# Buck_60W20V_Power_Section.net
KiCad netlist of a schematic drawn in Altium Designer
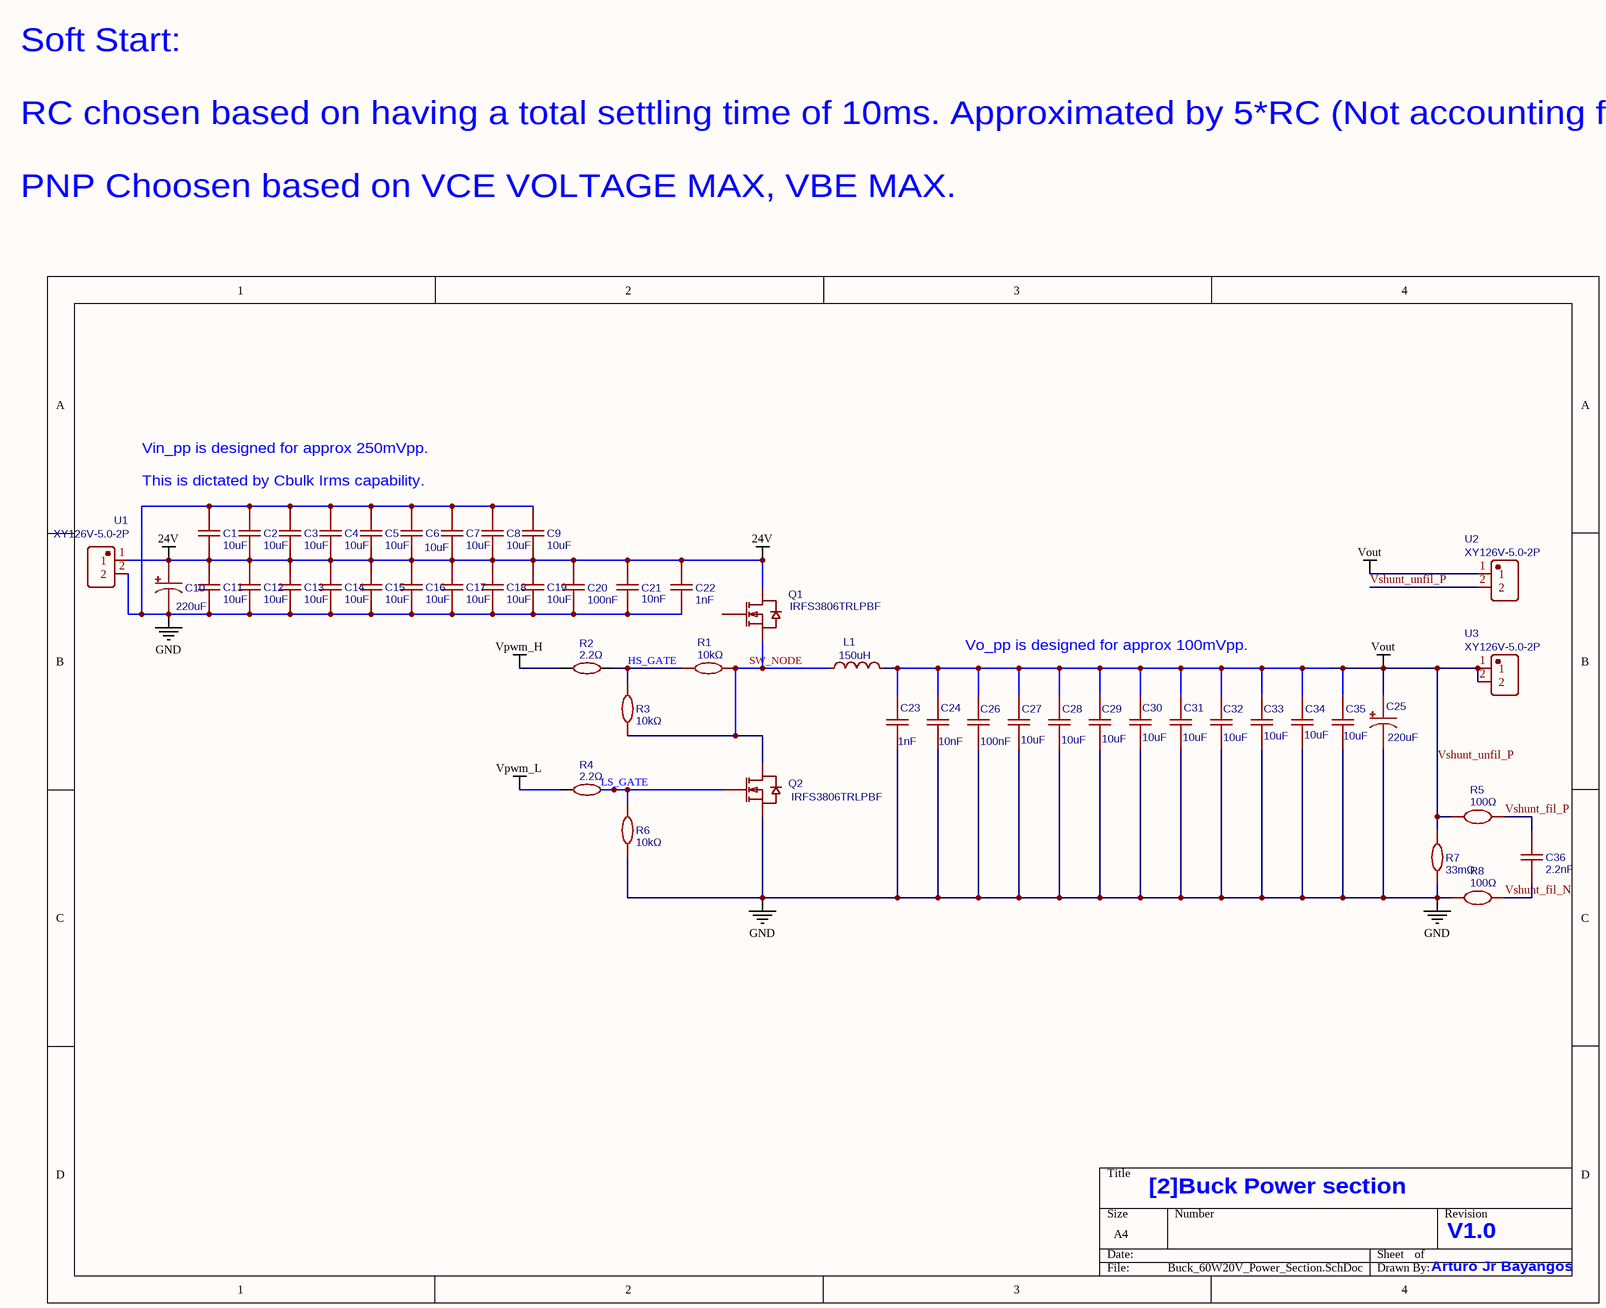
[diagram p0: Buck_60W20V_Power_Section.SchDoc]

(export (version "E")
  (design (tool "Eeschema 10.0.6"))
  (components
    (comp (ref "C1")
      (value "10uF")
      (footprint "C1210")
      (fields
        (field (name "MANUFACTURER") "TAIYO YUDEN(太诱)")
        (field (name "MANUFACTURER PART") "UMK325AB7106KM-T")
        (field (name "CONTRIBUTOR") "LCSC")
      )
      (libsource (lib "altium-import") (part "root_1_10uF_"))
    )
    (comp (ref "C2")
      (value "10uF")
      (footprint "C1210")
      (fields
        (field (name "MANUFACTURER") "TAIYO YUDEN(太诱)")
        (field (name "MANUFACTURER PART") "UMK325AB7106KM-T")
        (field (name "CONTRIBUTOR") "LCSC")
      )
      (libsource (lib "altium-import") (part "root_1_10uF_"))
    )
    (comp (ref "C3")
      (value "10uF")
      (footprint "C1210")
      (fields
        (field (name "MANUFACTURER") "TAIYO YUDEN(太诱)")
        (field (name "MANUFACTURER PART") "UMK325AB7106KM-T")
        (field (name "CONTRIBUTOR") "LCSC")
      )
      (libsource (lib "altium-import") (part "root_1_10uF_"))
    )
    (comp (ref "C4")
      (value "10uF")
      (footprint "C1210")
      (fields
        (field (name "MANUFACTURER") "TAIYO YUDEN(太诱)")
        (field (name "MANUFACTURER PART") "UMK325AB7106KM-T")
        (field (name "CONTRIBUTOR") "LCSC")
      )
      (libsource (lib "altium-import") (part "root_1_10uF_"))
    )
    (comp (ref "C5")
      (value "10uF")
      (footprint "C1210")
      (fields
        (field (name "MANUFACTURER") "TAIYO YUDEN(太诱)")
        (field (name "MANUFACTURER PART") "UMK325AB7106KM-T")
        (field (name "CONTRIBUTOR") "LCSC")
      )
      (libsource (lib "altium-import") (part "root_1_10uF_"))
    )
    (comp (ref "C6")
      (value "10uF")
      (footprint "C1210")
      (fields
        (field (name "MANUFACTURER") "TAIYO YUDEN(太诱)")
        (field (name "MANUFACTURER PART") "UMK325AB7106KM-T")
        (field (name "CONTRIBUTOR") "LCSC")
      )
      (libsource (lib "altium-import") (part "root_1_10uF_"))
    )
    (comp (ref "C7")
      (value "10uF")
      (footprint "C1210")
      (fields
        (field (name "MANUFACTURER") "TAIYO YUDEN(太诱)")
        (field (name "MANUFACTURER PART") "UMK325AB7106KM-T")
        (field (name "CONTRIBUTOR") "LCSC")
      )
      (libsource (lib "altium-import") (part "root_1_10uF_"))
    )
    (comp (ref "C8")
      (value "10uF")
      (footprint "C1210")
      (fields
        (field (name "MANUFACTURER") "TAIYO YUDEN(太诱)")
        (field (name "MANUFACTURER PART") "UMK325AB7106KM-T")
        (field (name "CONTRIBUTOR") "LCSC")
      )
      (libsource (lib "altium-import") (part "root_1_10uF_"))
    )
    (comp (ref "C9")
      (value "10uF")
      (footprint "C1210")
      (fields
        (field (name "MANUFACTURER") "TAIYO YUDEN(太诱)")
        (field (name "MANUFACTURER PART") "UMK325AB7106KM-T")
        (field (name "CONTRIBUTOR") "LCSC")
      )
      (libsource (lib "altium-import") (part "root_1_10uF_"))
    )
    (comp (ref "C10")
      (value "220uF")
      (footprint "CAP-SMD_BD10.0-L10.3-W10.3-LS11.3-FD")
      (fields
        (field (name "MANUFACTURER") "Nichicon(尼吉康)")
        (field (name "MANUFACTURER PART") "UUD1H221MNL1GS")
        (field (name "CONTRIBUTOR") "LCSC")
      )
      (libsource (lib "altium-import") (part "root_0_220uF_"))
    )
    (comp (ref "C11")
      (value "10uF")
      (footprint "C1210")
      (fields
        (field (name "MANUFACTURER") "TAIYO YUDEN(太诱)")
        (field (name "MANUFACTURER PART") "UMK325AB7106KM-T")
        (field (name "CONTRIBUTOR") "LCSC")
      )
      (libsource (lib "altium-import") (part "root_1_10uF_"))
    )
    (comp (ref "C12")
      (value "10uF")
      (footprint "C1210")
      (fields
        (field (name "MANUFACTURER") "TAIYO YUDEN(太诱)")
        (field (name "MANUFACTURER PART") "UMK325AB7106KM-T")
        (field (name "CONTRIBUTOR") "LCSC")
      )
      (libsource (lib "altium-import") (part "root_1_10uF_"))
    )
    (comp (ref "C13")
      (value "10uF")
      (footprint "C1210")
      (fields
        (field (name "MANUFACTURER") "TAIYO YUDEN(太诱)")
        (field (name "MANUFACTURER PART") "UMK325AB7106KM-T")
        (field (name "CONTRIBUTOR") "LCSC")
      )
      (libsource (lib "altium-import") (part "root_1_10uF_"))
    )
    (comp (ref "C14")
      (value "10uF")
      (footprint "C1210")
      (fields
        (field (name "MANUFACTURER") "TAIYO YUDEN(太诱)")
        (field (name "MANUFACTURER PART") "UMK325AB7106KM-T")
        (field (name "CONTRIBUTOR") "LCSC")
      )
      (libsource (lib "altium-import") (part "root_1_10uF_"))
    )
    (comp (ref "C15")
      (value "10uF")
      (footprint "C1210")
      (fields
        (field (name "MANUFACTURER") "TAIYO YUDEN(太诱)")
        (field (name "MANUFACTURER PART") "UMK325AB7106KM-T")
        (field (name "CONTRIBUTOR") "LCSC")
      )
      (libsource (lib "altium-import") (part "root_1_10uF_"))
    )
    (comp (ref "C16")
      (value "10uF")
      (footprint "C1210")
      (fields
        (field (name "MANUFACTURER") "TAIYO YUDEN(太诱)")
        (field (name "MANUFACTURER PART") "UMK325AB7106KM-T")
        (field (name "CONTRIBUTOR") "LCSC")
      )
      (libsource (lib "altium-import") (part "root_1_10uF_"))
    )
    (comp (ref "C17")
      (value "10uF")
      (footprint "C1210")
      (fields
        (field (name "MANUFACTURER") "TAIYO YUDEN(太诱)")
        (field (name "MANUFACTURER PART") "UMK325AB7106KM-T")
        (field (name "CONTRIBUTOR") "LCSC")
      )
      (libsource (lib "altium-import") (part "root_1_10uF_"))
    )
    (comp (ref "C18")
      (value "10uF")
      (footprint "C1210")
      (fields
        (field (name "MANUFACTURER") "TAIYO YUDEN(太诱)")
        (field (name "MANUFACTURER PART") "UMK325AB7106KM-T")
        (field (name "CONTRIBUTOR") "LCSC")
      )
      (libsource (lib "altium-import") (part "root_1_10uF_"))
    )
    (comp (ref "C19")
      (value "10uF")
      (footprint "C1210")
      (fields
        (field (name "MANUFACTURER") "TAIYO YUDEN(太诱)")
        (field (name "MANUFACTURER PART") "UMK325AB7106KM-T")
        (field (name "CONTRIBUTOR") "LCSC")
      )
      (libsource (lib "altium-import") (part "root_1_10uF_"))
    )
    (comp (ref "C20")
      (value "100nF")
      (footprint "C0402")
      (fields
        (field (name "MANUFACTURER") "TAIYO YUDEN(太诱)")
        (field (name "MANUFACTURER PART") "UMK105B7104KV-FR")
        (field (name "CONTRIBUTOR") "lcsc")
      )
      (libsource (lib "altium-import") (part "root_1_100nF_"))
    )
    (comp (ref "C21")
      (value "10nF")
      (footprint "C0402")
      (fields
        (field (name "MANUFACTURER") "TAIYO YUDEN(太诱)")
        (field (name "MANUFACTURER PART") "UMF105B7103KVHF")
        (field (name "CONTRIBUTOR") "LCSC")
      )
      (libsource (lib "altium-import") (part "root_0_10nF_"))
    )
    (comp (ref "C22")
      (value "1nF")
      (footprint "C0402")
      (fields
        (field (name "MANUFACTURER") "TAIYO YUDEN(太诱)")
        (field (name "MANUFACTURER PART") "UMF105B7102KVHF")
        (field (name "CONTRIBUTOR") "LCSC")
      )
      (libsource (lib "altium-import") (part "root_0_1nF_"))
    )
    (comp (ref "C23")
      (value "1nF")
      (footprint "C0402")
      (fields
        (field (name "MANUFACTURER") "TAIYO YUDEN(太诱)")
        (field (name "MANUFACTURER PART") "UMF105B7102KVHF")
        (field (name "CONTRIBUTOR") "LCSC")
      )
      (libsource (lib "altium-import") (part "root_0_1nF_"))
    )
    (comp (ref "C24")
      (value "10nF")
      (footprint "C0402")
      (fields
        (field (name "MANUFACTURER") "TAIYO YUDEN(太诱)")
        (field (name "MANUFACTURER PART") "UMF105B7103KVHF")
        (field (name "CONTRIBUTOR") "LCSC")
      )
      (libsource (lib "altium-import") (part "root_0_10nF_"))
    )
    (comp (ref "C25")
      (value "220uF")
      (footprint "CAP-SMD_BD10.0-L10.3-W10.3-LS11.3-FD")
      (fields
        (field (name "MANUFACTURER") "Nichicon(尼吉康)")
        (field (name "MANUFACTURER PART") "UUD1H221MNL1GS")
        (field (name "CONTRIBUTOR") "LCSC")
      )
      (libsource (lib "altium-import") (part "root_0_220uF_"))
    )
    (comp (ref "C26")
      (value "100nF")
      (footprint "C0402")
      (fields
        (field (name "MANUFACTURER") "TAIYO YUDEN(太诱)")
        (field (name "MANUFACTURER PART") "UMK105B7104KV-FR")
        (field (name "CONTRIBUTOR") "lcsc")
      )
      (libsource (lib "altium-import") (part "root_1_100nF_"))
    )
    (comp (ref "C27")
      (value "10uF")
      (footprint "C1210")
      (fields
        (field (name "MANUFACTURER") "TAIYO YUDEN(太诱)")
        (field (name "MANUFACTURER PART") "UMK325AB7106KM-T")
        (field (name "CONTRIBUTOR") "LCSC")
      )
      (libsource (lib "altium-import") (part "root_1_10uF_"))
    )
    (comp (ref "C28")
      (value "10uF")
      (footprint "C1210")
      (fields
        (field (name "MANUFACTURER") "TAIYO YUDEN(太诱)")
        (field (name "MANUFACTURER PART") "UMK325AB7106KM-T")
        (field (name "CONTRIBUTOR") "LCSC")
      )
      (libsource (lib "altium-import") (part "root_1_10uF_"))
    )
    (comp (ref "C29")
      (value "10uF")
      (footprint "C1210")
      (fields
        (field (name "MANUFACTURER") "TAIYO YUDEN(太诱)")
        (field (name "MANUFACTURER PART") "UMK325AB7106KM-T")
        (field (name "CONTRIBUTOR") "LCSC")
      )
      (libsource (lib "altium-import") (part "root_1_10uF_"))
    )
    (comp (ref "C30")
      (value "10uF")
      (footprint "C1210")
      (fields
        (field (name "MANUFACTURER") "TAIYO YUDEN(太诱)")
        (field (name "MANUFACTURER PART") "UMK325AB7106KM-T")
        (field (name "CONTRIBUTOR") "LCSC")
      )
      (libsource (lib "altium-import") (part "root_1_10uF_"))
    )
    (comp (ref "C31")
      (value "10uF")
      (footprint "C1210")
      (fields
        (field (name "MANUFACTURER") "TAIYO YUDEN(太诱)")
        (field (name "MANUFACTURER PART") "UMK325AB7106KM-T")
        (field (name "CONTRIBUTOR") "LCSC")
      )
      (libsource (lib "altium-import") (part "root_1_10uF_"))
    )
    (comp (ref "C32")
      (value "10uF")
      (footprint "C1210")
      (fields
        (field (name "MANUFACTURER") "TAIYO YUDEN(太诱)")
        (field (name "MANUFACTURER PART") "UMK325AB7106KM-T")
        (field (name "CONTRIBUTOR") "LCSC")
      )
      (libsource (lib "altium-import") (part "root_1_10uF_"))
    )
    (comp (ref "C33")
      (value "10uF")
      (footprint "C1210")
      (fields
        (field (name "MANUFACTURER") "TAIYO YUDEN(太诱)")
        (field (name "MANUFACTURER PART") "UMK325AB7106KM-T")
        (field (name "CONTRIBUTOR") "LCSC")
      )
      (libsource (lib "altium-import") (part "root_1_10uF_"))
    )
    (comp (ref "C34")
      (value "10uF")
      (footprint "C1210")
      (fields
        (field (name "MANUFACTURER") "TAIYO YUDEN(太诱)")
        (field (name "MANUFACTURER PART") "UMK325AB7106KM-T")
        (field (name "CONTRIBUTOR") "LCSC")
      )
      (libsource (lib "altium-import") (part "root_1_10uF_"))
    )
    (comp (ref "C35")
      (value "10uF")
      (footprint "C1210")
      (fields
        (field (name "MANUFACTURER") "TAIYO YUDEN(太诱)")
        (field (name "MANUFACTURER PART") "UMK325AB7106KM-T")
        (field (name "CONTRIBUTOR") "LCSC")
      )
      (libsource (lib "altium-import") (part "root_1_10uF_"))
    )
    (comp (ref "C36")
      (value "2.2nF")
      (footprint "C0603")
      (fields
        (field (name "MANUFACTURER") "TDK")
        (field (name "MANUFACTURER PART") "C1608C0G2E222JT000N")
        (field (name "CONTRIBUTOR") "LCSC")
      )
      (libsource (lib "altium-import") (part "root_1_2.2nF_"))
    )
    (comp (ref "L1")
      (value "150uH")
      (footprint "BUCK_INDUCTOR")
      (fields (field (name "CONTRIBUTOR") "LCEDA_Lib"))
      (libsource (lib "altium-import") (part "root_0_150uH_"))
    )
    (comp (ref "Q1")
      (value "IRFS3806TRLPBF")
      (footprint "D2PAK_L9.1-W10.0-P2.54-LS15.3-BR-1")
      (fields (field (name "MANUFACTURER") "Infineon(英飞凌)") (field (name "CONTRIBUTOR") "LCSC"))
      (libsource (lib "altium-import") (part "root_0_IRFS3806TRLPBF_"))
    )
    (comp (ref "Q2")
      (value "IRFS3806TRLPBF")
      (footprint "D2PAK_L9.1-W10.0-P2.54-LS15.3-BR-1")
      (fields (field (name "MANUFACTURER") "Infineon(英飞凌)") (field (name "CONTRIBUTOR") "LCSC"))
      (libsource (lib "altium-import") (part "root_0_IRFS3806TRLPBF_"))
    )
    (comp (ref "R1")
      (value "10kΩ")
      (footprint "R0603")
      (fields
        (field (name "MANUFACTURER") "Viking(光颉)")
        (field (name "MANUFACTURER PART") "ARG03BTC1002")
        (field (name "CONTRIBUTOR") "LCSC")
      )
      (libsource (lib "altium-import") (part "root_2_10kΩ_"))
    )
    (comp (ref "R2")
      (value "2.2Ω")
      (footprint "R0603")
      (fields
        (field (name "MANUFACTURER") "UNI-ROYAL(厚声)")
        (field (name "MANUFACTURER PART") "0603WAJ022JT5E")
      )
      (libsource (lib "altium-import") (part "root_0_2.2Ω_"))
    )
    (comp (ref "R3")
      (value "10kΩ")
      (footprint "R0603")
      (fields
        (field (name "MANUFACTURER") "Viking(光颉)")
        (field (name "MANUFACTURER PART") "ARG03BTC1002")
        (field (name "CONTRIBUTOR") "LCSC")
      )
      (libsource (lib "altium-import") (part "root_1_10kΩ_"))
    )
    (comp (ref "R4")
      (value "2.2Ω")
      (footprint "R0603")
      (fields
        (field (name "MANUFACTURER") "UNI-ROYAL(厚声)")
        (field (name "MANUFACTURER PART") "0603WAJ022JT5E")
      )
      (libsource (lib "altium-import") (part "root_0_2.2Ω_"))
    )
    (comp (ref "R5")
      (value "100Ω")
      (footprint "R0603")
      (fields
        (field (name "MANUFACTURER") "YAGEO(国巨)")
        (field (name "MANUFACTURER PART") "RT0603CRE07100RL")
        (field (name "CONTRIBUTOR") "LCSC")
      )
      (libsource (lib "altium-import") (part "root_0_100Ω_"))
    )
    (comp (ref "R6")
      (value "10kΩ")
      (footprint "R0603")
      (fields
        (field (name "MANUFACTURER") "Viking(光颉)")
        (field (name "MANUFACTURER PART") "ARG03BTC1002")
        (field (name "CONTRIBUTOR") "LCSC")
      )
      (libsource (lib "altium-import") (part "root_1_10kΩ_"))
    )
    (comp (ref "R7")
      (value "33mΩ")
      (footprint "R1210")
      (fields
        (field (name "MANUFACTURER") "RALEC(旺诠)")
        (field (name "MANUFACTURER PART") "RTT12R033FTP")
        (field (name "CONTRIBUTOR") "LCSC")
      )
      (libsource (lib "altium-import") (part "root_3_33mΩ_"))
    )
    (comp (ref "R8")
      (value "100Ω")
      (footprint "R0603")
      (fields
        (field (name "MANUFACTURER") "YAGEO(国巨)")
        (field (name "MANUFACTURER PART") "RT0603CRE07100RL")
        (field (name "CONTRIBUTOR") "LCSC")
      )
      (libsource (lib "altium-import") (part "root_0_100Ω_"))
    )
    (comp (ref "U1")
      (value "XY126V-5.0-2P")
      (footprint "CONN-TH_XY126V-5.0-2P")
      (fields (field (name "MANUFACTURER") "XINLAIYA(新莱亚)") (field (name "CONTRIBUTOR") "LCSC"))
      (libsource (lib "") (part "root_0_XY126V-5.0-2P__1"))
    )
    (comp (ref "U2")
      (value "XY126V-5.0-2P")
      (footprint "CONN-TH_XY126V-5.0-2P")
      (fields (field (name "MANUFACTURER") "XINLAIYA(新莱亚)") (field (name "CONTRIBUTOR") "LCSC"))
      (libsource (lib "altium-import") (part "root_0_XY126V-5.0-2P_"))
    )
    (comp (ref "U3")
      (value "XY126V-5.0-2P")
      (footprint "CONN-TH_XY126V-5.0-2P")
      (fields (field (name "MANUFACTURER") "XINLAIYA(新莱亚)") (field (name "CONTRIBUTOR") "LCSC"))
      (libsource (lib "altium-import") (part "root_0_XY126V-5.0-2P_"))
    )
  )
  (nets
    (net (code "1") (name "/HS_GATE") (class "Default")
      (node (ref "R1") (pin "2") (pinfunction "2_2") (pintype "passive"))
      (node (ref "R2") (pin "2") (pinfunction "2_2") (pintype "passive"))
      (node (ref "R3") (pin "2") (pinfunction "2_2") (pintype "passive"))
    )
    (net (code "2") (name "/LS_GATE") (class "Default")
      (node (ref "Q2") (pin "1") (pinfunction "G_1") (pintype "passive"))
      (node (ref "R4") (pin "2") (pinfunction "2_2") (pintype "passive"))
      (node (ref "R6") (pin "2") (pinfunction "2_2") (pintype "passive"))
    )
    (net (code "3") (name "/SW_NODE") (class "Default")
      (node (ref "L1") (pin "1") (pinfunction "1_1") (pintype "passive"))
      (node (ref "Q1") (pin "3") (pinfunction "S_3") (pintype "passive"))
      (node (ref "Q2") (pin "4") (pinfunction "D_4") (pintype "passive"))
      (node (ref "R1") (pin "1") (pinfunction "1_1") (pintype "passive"))
      (node (ref "R3") (pin "1") (pinfunction "1_1") (pintype "passive"))
    )
    (net (code "4") (name "/Vshunt_fil_N") (class "Default")
      (node (ref "C36") (pin "1") (pinfunction "1_1") (pintype "passive"))
      (node (ref "R8") (pin "2") (pinfunction "2_2") (pintype "passive"))
    )
    (net (code "5") (name "/Vshunt_fil_P") (class "Default")
      (node (ref "C36") (pin "2") (pinfunction "2_2") (pintype "passive"))
      (node (ref "R5") (pin "2") (pinfunction "2_2") (pintype "passive"))
    )
    (net (code "6") (name "24V") (class "Default")
      (node (ref "C1") (pin "1") (pinfunction "1_1") (pintype "passive"))
      (node (ref "C10") (pin "1") (pinfunction "1_1") (pintype "passive"))
      (node (ref "C11") (pin "2") (pinfunction "2_2") (pintype "passive"))
      (node (ref "C12") (pin "2") (pinfunction "2_2") (pintype "passive"))
      (node (ref "C13") (pin "2") (pinfunction "2_2") (pintype "passive"))
      (node (ref "C14") (pin "2") (pinfunction "2_2") (pintype "passive"))
      (node (ref "C15") (pin "2") (pinfunction "2_2") (pintype "passive"))
      (node (ref "C16") (pin "2") (pinfunction "2_2") (pintype "passive"))
      (node (ref "C17") (pin "2") (pinfunction "2_2") (pintype "passive"))
      (node (ref "C18") (pin "2") (pinfunction "2_2") (pintype "passive"))
      (node (ref "C19") (pin "2") (pinfunction "2_2") (pintype "passive"))
      (node (ref "C2") (pin "1") (pinfunction "1_1") (pintype "passive"))
      (node (ref "C20") (pin "2") (pinfunction "2_2") (pintype "passive"))
      (node (ref "C21") (pin "2") (pinfunction "2_2") (pintype "passive"))
      (node (ref "C22") (pin "2") (pinfunction "2_2") (pintype "passive"))
      (node (ref "C3") (pin "1") (pinfunction "1_1") (pintype "passive"))
      (node (ref "C4") (pin "1") (pinfunction "1_1") (pintype "passive"))
      (node (ref "C5") (pin "1") (pinfunction "1_1") (pintype "passive"))
      (node (ref "C6") (pin "1") (pinfunction "1_1") (pintype "passive"))
      (node (ref "C7") (pin "1") (pinfunction "1_1") (pintype "passive"))
      (node (ref "C8") (pin "1") (pinfunction "1_1") (pintype "passive"))
      (node (ref "C9") (pin "1") (pinfunction "1_1") (pintype "passive"))
      (node (ref "Q1") (pin "4") (pinfunction "D_4") (pintype "passive"))
      (node (ref "U1") (pin "1") (pinfunction "1_1") (pintype "passive"))
    )
    (net (code "7") (name "GND") (class "Default")
      (node (ref "C1") (pin "2") (pinfunction "2_2") (pintype "passive"))
      (node (ref "C10") (pin "2") (pinfunction "2_2") (pintype "passive"))
      (node (ref "C11") (pin "1") (pinfunction "1_1") (pintype "passive"))
      (node (ref "C12") (pin "1") (pinfunction "1_1") (pintype "passive"))
      (node (ref "C13") (pin "1") (pinfunction "1_1") (pintype "passive"))
      (node (ref "C14") (pin "1") (pinfunction "1_1") (pintype "passive"))
      (node (ref "C15") (pin "1") (pinfunction "1_1") (pintype "passive"))
      (node (ref "C16") (pin "1") (pinfunction "1_1") (pintype "passive"))
      (node (ref "C17") (pin "1") (pinfunction "1_1") (pintype "passive"))
      (node (ref "C18") (pin "1") (pinfunction "1_1") (pintype "passive"))
      (node (ref "C19") (pin "1") (pinfunction "1_1") (pintype "passive"))
      (node (ref "C2") (pin "2") (pinfunction "2_2") (pintype "passive"))
      (node (ref "C20") (pin "1") (pinfunction "1_1") (pintype "passive"))
      (node (ref "C21") (pin "1") (pinfunction "1_1") (pintype "passive"))
      (node (ref "C22") (pin "1") (pinfunction "1_1") (pintype "passive"))
      (node (ref "C23") (pin "1") (pinfunction "1_1") (pintype "passive"))
      (node (ref "C24") (pin "1") (pinfunction "1_1") (pintype "passive"))
      (node (ref "C25") (pin "2") (pinfunction "2_2") (pintype "passive"))
      (node (ref "C26") (pin "1") (pinfunction "1_1") (pintype "passive"))
      (node (ref "C27") (pin "1") (pinfunction "1_1") (pintype "passive"))
      (node (ref "C28") (pin "1") (pinfunction "1_1") (pintype "passive"))
      (node (ref "C29") (pin "1") (pinfunction "1_1") (pintype "passive"))
      (node (ref "C3") (pin "2") (pinfunction "2_2") (pintype "passive"))
      (node (ref "C30") (pin "1") (pinfunction "1_1") (pintype "passive"))
      (node (ref "C31") (pin "1") (pinfunction "1_1") (pintype "passive"))
      (node (ref "C32") (pin "1") (pinfunction "1_1") (pintype "passive"))
      (node (ref "C33") (pin "1") (pinfunction "1_1") (pintype "passive"))
      (node (ref "C34") (pin "1") (pinfunction "1_1") (pintype "passive"))
      (node (ref "C35") (pin "1") (pinfunction "1_1") (pintype "passive"))
      (node (ref "C4") (pin "2") (pinfunction "2_2") (pintype "passive"))
      (node (ref "C5") (pin "2") (pinfunction "2_2") (pintype "passive"))
      (node (ref "C6") (pin "2") (pinfunction "2_2") (pintype "passive"))
      (node (ref "C7") (pin "2") (pinfunction "2_2") (pintype "passive"))
      (node (ref "C8") (pin "2") (pinfunction "2_2") (pintype "passive"))
      (node (ref "C9") (pin "2") (pinfunction "2_2") (pintype "passive"))
      (node (ref "Q2") (pin "3") (pinfunction "S_3") (pintype "passive"))
      (node (ref "R6") (pin "1") (pinfunction "1_1") (pintype "passive"))
      (node (ref "R7") (pin "1") (pinfunction "1_1") (pintype "passive"))
      (node (ref "R8") (pin "1") (pinfunction "1_1") (pintype "passive"))
      (node (ref "U1") (pin "2") (pinfunction "2_2") (pintype "passive"))
    )
    (net (code "8") (name "Vout") (class "Default")
      (node (ref "C23") (pin "2") (pinfunction "2_2") (pintype "passive"))
      (node (ref "C24") (pin "2") (pinfunction "2_2") (pintype "passive"))
      (node (ref "C25") (pin "1") (pinfunction "1_1") (pintype "passive"))
      (node (ref "C26") (pin "2") (pinfunction "2_2") (pintype "passive"))
      (node (ref "C27") (pin "2") (pinfunction "2_2") (pintype "passive"))
      (node (ref "C28") (pin "2") (pinfunction "2_2") (pintype "passive"))
      (node (ref "C29") (pin "2") (pinfunction "2_2") (pintype "passive"))
      (node (ref "C30") (pin "2") (pinfunction "2_2") (pintype "passive"))
      (node (ref "C31") (pin "2") (pinfunction "2_2") (pintype "passive"))
      (node (ref "C32") (pin "2") (pinfunction "2_2") (pintype "passive"))
      (node (ref "C33") (pin "2") (pinfunction "2_2") (pintype "passive"))
      (node (ref "C34") (pin "2") (pinfunction "2_2") (pintype "passive"))
      (node (ref "C35") (pin "2") (pinfunction "2_2") (pintype "passive"))
      (node (ref "L1") (pin "2") (pinfunction "2_2") (pintype "passive"))
      (node (ref "R5") (pin "1") (pinfunction "1_1") (pintype "passive"))
      (node (ref "R7") (pin "2") (pinfunction "2_2") (pintype "passive"))
      (node (ref "U2") (pin "1") (pinfunction "1_1") (pintype "passive"))
      (node (ref "U2") (pin "2") (pinfunction "2_2") (pintype "passive"))
      (node (ref "U3") (pin "1") (pinfunction "1_1") (pintype "passive"))
      (node (ref "U3") (pin "2") (pinfunction "2_2") (pintype "passive"))
    )
    (net (code "9") (name "Vpwm_H") (class "Default")
      (node (ref "R2") (pin "1") (pinfunction "1_1") (pintype "passive"))
    )
    (net (code "10") (name "Vpwm_L") (class "Default")
      (node (ref "R4") (pin "1") (pinfunction "1_1") (pintype "passive"))
    )
    (net (code "11") (name "unconnected-(Q1-G-Pad1)") (class "Default")
      (node (ref "Q1") (pin "1") (pinfunction "G_1") (pintype "passive"))
    )
  )
)
